# 5VBulkhead.net
KiCad netlist of a schematic drawn in Altium Designer
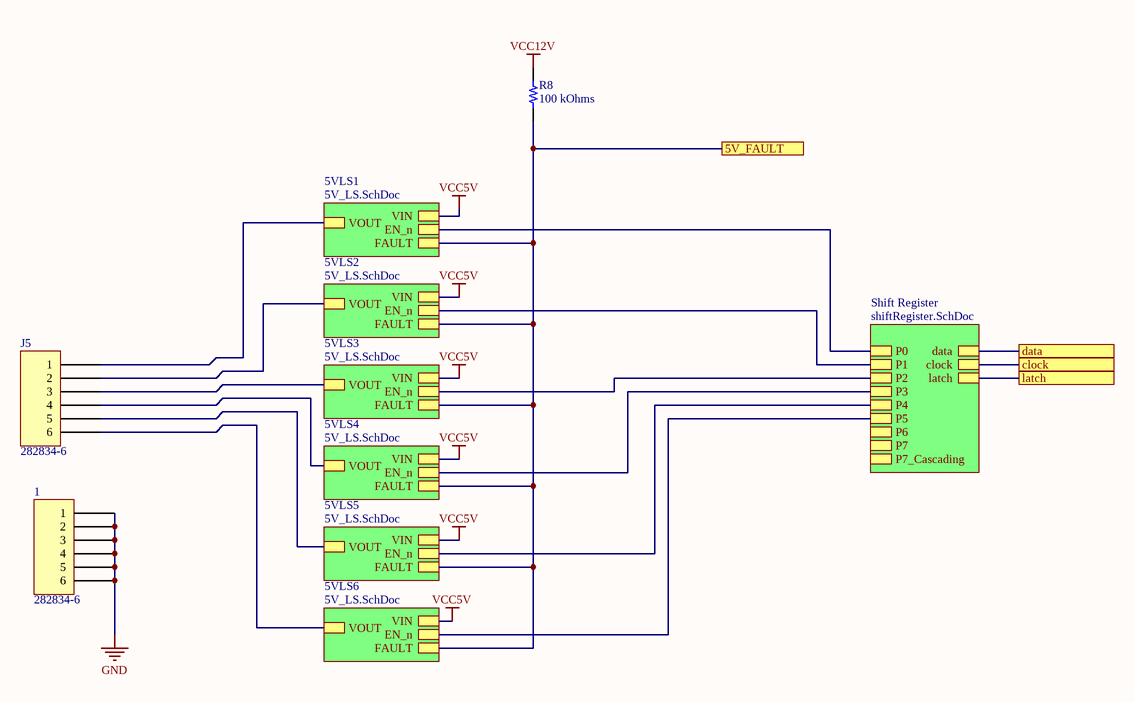
[diagram p0: 5VBulkhead.SchDoc]

(export (version "E")
  (design (tool "Eeschema 10.0.6"))
  (components
    (comp (ref "1")
      (value "282834-6")
      (footprint "TE 282834-6")
      (description "TERM BLK 6P SIDE ENT 2.54MM PCB")
      (fields (field (name "MANUFACTURER") "TE Connectivity AMP Connectors") (field (name "VOLTAGE") "150V"))
      (libsource (lib "Celestial Altium Library - altium_library") (part "6 Pin"))
    )
    (comp (ref "J5")
      (value "282834-6")
      (footprint "TE 282834-6")
      (description "TERM BLK 6P SIDE ENT 2.54MM PCB")
      (fields (field (name "MANUFACTURER") "TE Connectivity AMP Connectors") (field (name "VOLTAGE") "150V"))
      (libsource (lib "Celestial Altium Library - altium_library") (part "6 Pin"))
    )
    (comp (ref "R8")
      (value "100 kOhms")
      (footprint "RES 0603_1608")
      (description "RES 100K OHM 0.1% 1/16W 0603")
      (fields
        (field (name "PART NUMBER") "RNCS0603BKE100K")
        (field (name "MANUFACTURER") "Stackpole Electronics Inc")
      )
      (libsource (lib "Celestial Altium Library - altium_library") (part "Resistor"))
    )
  )
  (nets
    (net (code "1") (name "/5V_FAULT") (class "Default")
      (node (ref "R8") (pin "1") (pinfunction "1_1") (pintype "passive"))
    )
    (net (code "11") (name "/VOUT") (class "Default")
      (node (ref "J5") (pin "1") (pinfunction "1_1") (pintype "passive"))
    )
    (net (code "12") (name "/VOUT_1") (class "Default")
      (node (ref "J5") (pin "2") (pinfunction "2_2") (pintype "passive"))
    )
    (net (code "13") (name "/VOUT_2") (class "Default")
      (node (ref "J5") (pin "3") (pinfunction "3_3") (pintype "passive"))
    )
    (net (code "14") (name "/VOUT_3") (class "Default")
      (node (ref "J5") (pin "4") (pinfunction "4_4") (pintype "passive"))
    )
    (net (code "15") (name "/VOUT_4") (class "Default")
      (node (ref "J5") (pin "5") (pinfunction "5_5") (pintype "passive"))
    )
    (net (code "16") (name "/VOUT_5") (class "Default")
      (node (ref "J5") (pin "6") (pinfunction "6_6") (pintype "passive"))
    )
    (net (code "20") (name "GND") (class "Default")
      (node (ref "1") (pin "1") (pinfunction "1_1") (pintype "passive"))
      (node (ref "1") (pin "2") (pinfunction "2_2") (pintype "passive"))
      (node (ref "1") (pin "3") (pinfunction "3_3") (pintype "passive"))
      (node (ref "1") (pin "4") (pinfunction "4_4") (pintype "passive"))
      (node (ref "1") (pin "5") (pinfunction "5_5") (pintype "passive"))
      (node (ref "1") (pin "6") (pinfunction "6_6") (pintype "passive"))
    )
    (net (code "22") (name "VCC12V") (class "Default")
      (node (ref "R8") (pin "2") (pinfunction "2_2") (pintype "passive"))
    )
  )
)
